# Power.net
KiCad netlist of a schematic drawn in Altium Designer
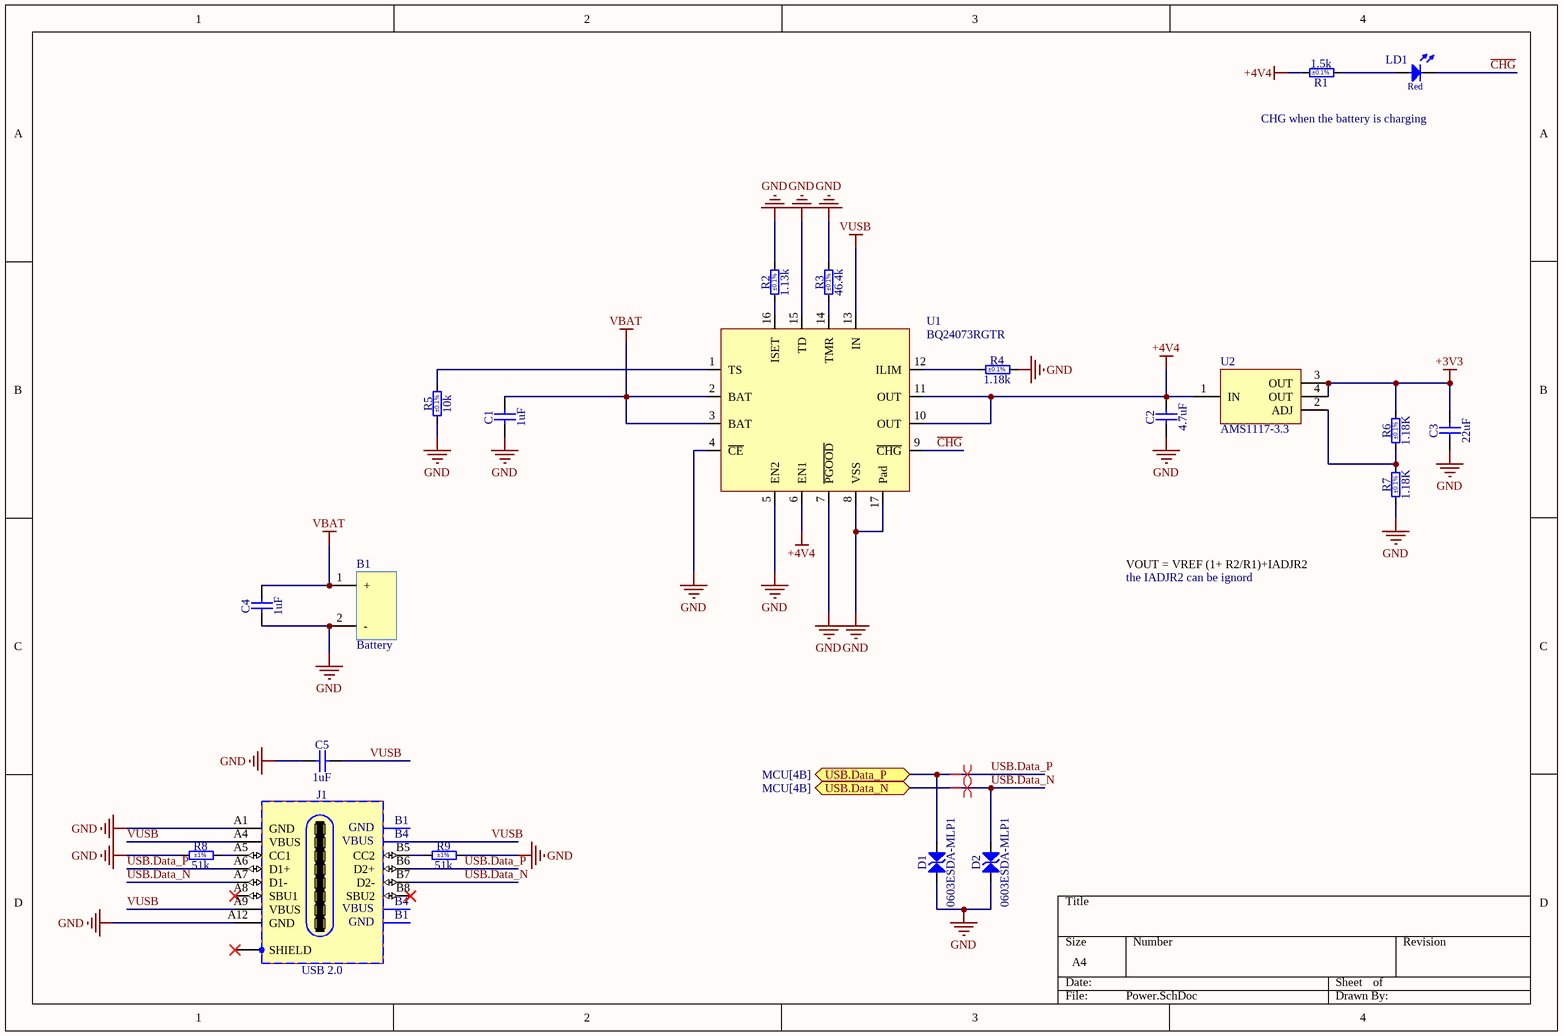
[diagram p0: Power.SchDoc]

(export (version "E")
  (design (tool "Eeschema 10.0.6"))
  (components
    (comp (ref "B1")
      (value "Battery")
      (footprint "PCB.Battery.Holder.14500")
      (description "PCB Battery Holder Embeded in PCB")
      (libsource (lib "ParsaAltiumSCHLIB") (part "PCB.Battery.Holder.14500"))
    )
    (comp (ref "C1")
      (value "1uF")
      (footprint "CAPC1608X90N")
      (description "Non-polarised capacitor")
      (fields
        (field (name "PART NUMBER") "CC0603_1UF_10V_10%_X5R")
        (field (name "VOLTAGE") "10V")
        (field (name "AUTHOR") "CERN DEM HF")
      )
      (libsource (lib "Capacitors") (part "Capacitor - non polarized"))
    )
    (comp (ref "C2")
      (value "4.7uF")
      (footprint "CAPC1608X90N")
      (description "Non-polarised capacitor")
      (fields
        (field (name "PART NUMBER") "CC0603_4.7UF_10V_10%_X5R")
        (field (name "VOLTAGE") "10V")
        (field (name "AUTHOR") "CERN DEM HF")
      )
      (libsource (lib "Capacitors") (part "Capacitor - non polarized"))
    )
    (comp (ref "C3")
      (value "22uF")
      (footprint "CAPC1608X90N")
      (description "Non-polarised capacitor")
      (fields
        (field (name "PART NUMBER") "CC0603_22UF_10V_20%_X5R")
        (field (name "VOLTAGE") "10V")
        (field (name "AUTHOR") "CERN DEM BC")
      )
      (libsource (lib "Capacitors") (part "Capacitor - non polarized"))
    )
    (comp (ref "C4")
      (value "1uF")
      (footprint "CAPC1608X90N")
      (description "Non-polarised capacitor")
      (fields
        (field (name "PART NUMBER") "CC0603_1UF_10V_10%_X5R")
        (field (name "VOLTAGE") "10V")
        (field (name "AUTHOR") "CERN DEM HF")
      )
      (libsource (lib "Capacitors") (part "Capacitor - non polarized"))
    )
    (comp (ref "C5")
      (value "1uF")
      (footprint "CAPC1608X90N")
      (description "Non-polarised capacitor")
      (fields
        (field (name "PART NUMBER") "CC0603_1UF_10V_10%_X5R")
        (field (name "VOLTAGE") "10V")
        (field (name "AUTHOR") "CERN DEM HF")
      )
      (libsource (lib "Capacitors") (part "Capacitor - non polarized"))
    )
    (comp (ref "D1")
      (value "0603ESDA-MLP1")
      (footprint "EATON_0603ESDA-MLP")
      (description "Transient Voltage Suppressor Diode (Bi-Directional)")
      (fields
        (field (name "VOLTAGE") "8kV")
        (field (name "MANUFACTURER") "EATON")
        (field (name "AUTHOR") "CERN DEM HF")
      )
      (libsource (lib "ICs And Semiconductors") (part "Diode TVS Bi-Directional"))
    )
    (comp (ref "D2")
      (value "0603ESDA-MLP1")
      (footprint "EATON_0603ESDA-MLP")
      (description "Transient Voltage Suppressor Diode (Bi-Directional)")
      (fields
        (field (name "VOLTAGE") "8kV")
        (field (name "MANUFACTURER") "EATON")
        (field (name "AUTHOR") "CERN DEM HF")
      )
      (libsource (lib "ICs And Semiconductors") (part "Diode TVS Bi-Directional"))
    )
    (comp (ref "J1")
      (value "USB 2.0")
      (footprint "GCT_USB4105-GF-A")
      (description "2x8 Pin + 1 Shield  USB Type C Receptacle")
      (fields
        (field (name "PART NUMBER") "GCT_USB4105-GF-A")
        (field (name "MANUFACTURER") "GCT")
        (field (name "AUTHOR") "CERN DEM HF")
      )
      (libsource (lib "Connectors") (part "GCT_USB4105-GF-A"))
    )
    (comp (ref "LD1")
      (value "Red")
      (footprint "LED_DIALIGHT_598-8010-107F")
      (description "LED Red 1C 2A")
      (fields
        (field (name "PART NUMBER") "LED_DIALIGHT_598-8010-107F")
        (field (name "MANUFACTURER") "DIALIGHT")
        (field (name "AUTHOR") "CERN DEM MR")
      )
      (libsource (lib "ICs And Semiconductors") (part "LED Red 1C 2A"))
    )
    (comp (ref "R1")
      (value "1.5k")
      (footprint "RESC1608X55N")
      (description "Resistor - 0.1%")
      (fields
        (field (name "TOLERANCE") "±0.1%")
        (field (name "PART NUMBER") "R0603_10K_0.1%_0.063W_10PPM")
        (field (name "POWER") "0.063W")
        (field (name "AUTHOR") "CERN DEM JLC")
      )
      (libsource (lib "Resistors") (part "Resistor - 0.1%"))
    )
    (comp (ref "R2")
      (value "1.13k")
      (footprint "RESC1608X55N")
      (description "Resistor - 0.1%")
      (fields
        (field (name "TOLERANCE") "±0.1%")
        (field (name "PART NUMBER") "R0603_10K_0.1%_0.063W_10PPM")
        (field (name "POWER") "0.063W")
        (field (name "AUTHOR") "CERN DEM JLC")
      )
      (libsource (lib "Resistors") (part "Resistor - 0.1%"))
    )
    (comp (ref "R3")
      (value "46.4k")
      (footprint "RESC1608X55N")
      (description "Resistor - 0.1%")
      (fields
        (field (name "TOLERANCE") "±0.1%")
        (field (name "PART NUMBER") "R0603_10K_0.1%_0.063W_10PPM")
        (field (name "POWER") "0.063W")
        (field (name "AUTHOR") "CERN DEM JLC")
      )
      (libsource (lib "Resistors") (part "Resistor - 0.1%"))
    )
    (comp (ref "R4")
      (value "1.18k")
      (footprint "RESC1608X55N")
      (description "Resistor - 0.1%")
      (fields
        (field (name "TOLERANCE") "±0.1%")
        (field (name "PART NUMBER") "R0603_10K_0.1%_0.063W_10PPM")
        (field (name "POWER") "0.063W")
        (field (name "AUTHOR") "CERN DEM JLC")
      )
      (libsource (lib "Resistors") (part "Resistor - 0.1%"))
    )
    (comp (ref "R5")
      (value "10k")
      (footprint "RESC1608X55N")
      (description "Resistor - 0.1%")
      (fields
        (field (name "TOLERANCE") "±0.1%")
        (field (name "PART NUMBER") "R0603_10K_0.1%_0.063W_10PPM")
        (field (name "POWER") "0.063W")
        (field (name "AUTHOR") "CERN DEM JLC")
      )
      (libsource (lib "Resistors") (part "Resistor - 0.1%"))
    )
    (comp (ref "R6")
      (value "1.18K")
      (footprint "RESC1608X55N")
      (description "Resistor - 0.1%")
      (fields
        (field (name "TOLERANCE") "±0.1%")
        (field (name "PART NUMBER") "R0603_118R_0.1%_0.063W_10PPM")
        (field (name "POWER") "0.063W")
        (field (name "AUTHOR") "CERN DEM JLC")
      )
      (libsource (lib "Resistors") (part "Resistor - 0.1%"))
    )
    (comp (ref "R7")
      (value "1.18K")
      (footprint "RESC1608X55N")
      (description "Resistor - 0.1%")
      (fields
        (field (name "TOLERANCE") "±0.1%")
        (field (name "PART NUMBER") "R0603_118R_0.1%_0.063W_10PPM")
        (field (name "POWER") "0.063W")
        (field (name "AUTHOR") "CERN DEM JLC")
      )
      (libsource (lib "Resistors") (part "Resistor - 0.1%"))
    )
    (comp (ref "R8")
      (value "51k")
      (footprint "RESC1608X55N")
      (description "Resistor - 1%")
      (fields
        (field (name "TOLERANCE") "±1%")
        (field (name "PART NUMBER") "R0603_51K_1%_0.1W_100PPM")
        (field (name "POWER") "0.1W")
        (field (name "AUTHOR") "CERN DEM JLC")
      )
      (libsource (lib "Resistors") (part "Resistor - 1%"))
    )
    (comp (ref "R9")
      (value "51k")
      (footprint "RESC1608X55N")
      (description "Resistor - 1%")
      (fields
        (field (name "TOLERANCE") "±1%")
        (field (name "PART NUMBER") "R0603_51K_1%_0.1W_100PPM")
        (field (name "POWER") "0.1W")
        (field (name "AUTHOR") "CERN DEM JLC")
      )
      (libsource (lib "Resistors") (part "Resistor - 1%"))
    )
    (comp (ref "U1")
      (value "BQ24073RGTR")
      (footprint "bq24073")
      (description "1.5A USB-FRIENDLY Li-Ion BATTERY CHARGER AND POWER-PATH MANAGEMENT IC")
      (libsource (lib "Schlib1") (part "BQ24073RGTR"))
    )
    (comp (ref "U2")
      (value "AMS1117-3.3")
      (footprint "IC.AMS1117-3.3")
      (description "72dB@(120Hz) 1A Fixed 3.3V Positive electrode SOT-223-3 Linear Voltage Regulators (LDO) ROHS")
      (libsource (lib "ParsaAltiumSCHLIB") (part "IC.AMS1117-3.3"))
    )
  )
  (nets
    (net (code "1") (name "+3V3") (class "Default")
      (node (ref "C3") (pin "2") (pinfunction "2_2") (pintype "passive"))
      (node (ref "R6") (pin "2") (pinfunction "2_2") (pintype "passive"))
      (node (ref "U2") (pin "3") (pinfunction "OUT_3") (pintype "passive"))
      (node (ref "U2") (pin "4") (pinfunction "OUT_4") (pintype "passive"))
    )
    (net (code "2") (name "+4V4") (class "Default")
      (node (ref "C2") (pin "2") (pinfunction "2_2") (pintype "passive"))
      (node (ref "R1") (pin "2") (pinfunction "2_2") (pintype "passive"))
      (node (ref "U1") (pin "10") (pinfunction "OUT_10") (pintype "passive"))
      (node (ref "U1") (pin "11") (pinfunction "OUT_11") (pintype "passive"))
      (node (ref "U1") (pin "6") (pinfunction "EN1_6") (pintype "passive"))
      (node (ref "U2") (pin "1") (pinfunction "IN_1") (pintype "passive"))
    )
    (net (code "3") (name "/USB.Data_N") (class "Default")
      (node (ref "D2") (pin "2") (pinfunction "2_2") (pintype "passive"))
      (node (ref "J1") (pin "A7") (pinfunction "D1-_A7") (pintype "bidirectional"))
      (node (ref "J1") (pin "B7") (pinfunction "D2-_B7") (pintype "bidirectional"))
    )
    (net (code "4") (name "/USB.Data_P") (class "Default")
      (node (ref "D1") (pin "2") (pinfunction "2_2") (pintype "passive"))
      (node (ref "J1") (pin "A6") (pinfunction "D1+_A6") (pintype "bidirectional"))
      (node (ref "J1") (pin "B6") (pinfunction "D2+_B6") (pintype "bidirectional"))
    )
    (net (code "5") (name "/~{CHG}") (class "Default")
      (node (ref "LD1") (pin "1") (pinfunction "C_1") (pintype "passive"))
      (node (ref "U1") (pin "9") (pinfunction "~{CHG}_9") (pintype "passive"))
    )
    (net (code "6") (name "GND") (class "Default")
      (node (ref "B1") (pin "2") (pinfunction "-_2") (pintype "passive"))
      (node (ref "C1") (pin "1") (pinfunction "1_1") (pintype "passive"))
      (node (ref "C2") (pin "1") (pinfunction "1_1") (pintype "passive"))
      (node (ref "C3") (pin "1") (pinfunction "1_1") (pintype "passive"))
      (node (ref "C4") (pin "1") (pinfunction "1_1") (pintype "passive"))
      (node (ref "C5") (pin "1") (pinfunction "1_1") (pintype "passive"))
      (node (ref "D1") (pin "1") (pinfunction "1_1") (pintype "passive"))
      (node (ref "D2") (pin "1") (pinfunction "1_1") (pintype "passive"))
      (node (ref "J1") (pin "A1") (pinfunction "GND_A1") (pintype "power_in"))
      (node (ref "J1") (pin "A12") (pinfunction "GND_A12") (pintype "power_in"))
      (node (ref "R2") (pin "2") (pinfunction "2_2") (pintype "passive"))
      (node (ref "R3") (pin "2") (pinfunction "2_2") (pintype "passive"))
      (node (ref "R4") (pin "2") (pinfunction "2_2") (pintype "passive"))
      (node (ref "R5") (pin "1") (pinfunction "1_1") (pintype "passive"))
      (node (ref "R7") (pin "1") (pinfunction "1_1") (pintype "passive"))
      (node (ref "R8") (pin "1") (pinfunction "1_1") (pintype "passive"))
      (node (ref "R9") (pin "2") (pinfunction "2_2") (pintype "passive"))
      (node (ref "U1") (pin "15") (pinfunction "TD_15") (pintype "passive"))
      (node (ref "U1") (pin "17") (pinfunction "Pad_17") (pintype "passive"))
      (node (ref "U1") (pin "4") (pinfunction "~{CE}_4") (pintype "passive"))
      (node (ref "U1") (pin "5") (pinfunction "EN2_5") (pintype "passive"))
      (node (ref "U1") (pin "7") (pinfunction "~{PGOOD}_7") (pintype "passive"))
      (node (ref "U1") (pin "8") (pinfunction "VSS_8") (pintype "passive"))
    )
    (net (code "7") (name "Net-(J1-CC1)") (class "Default")
      (node (ref "J1") (pin "A5") (pinfunction "CC1_A5") (pintype "bidirectional"))
      (node (ref "R8") (pin "2") (pinfunction "2_2") (pintype "passive"))
    )
    (net (code "8") (name "Net-(J1-CC2)") (class "Default")
      (node (ref "J1") (pin "B5") (pinfunction "CC2_B5") (pintype "bidirectional"))
      (node (ref "R9") (pin "1") (pinfunction "1_1") (pintype "passive"))
    )
    (net (code "9") (name "Net-(LD1-A)") (class "Default")
      (node (ref "LD1") (pin "2") (pinfunction "A_2") (pintype "passive"))
      (node (ref "R1") (pin "1") (pinfunction "1_1") (pintype "passive"))
    )
    (net (code "10") (name "Net-(U1-ILIM)") (class "Default")
      (node (ref "R4") (pin "1") (pinfunction "1_1") (pintype "passive"))
      (node (ref "U1") (pin "12") (pinfunction "ILIM_12") (pintype "passive"))
    )
    (net (code "11") (name "Net-(U1-ISET)") (class "Default")
      (node (ref "R2") (pin "1") (pinfunction "1_1") (pintype "passive"))
      (node (ref "U1") (pin "16") (pinfunction "ISET_16") (pintype "passive"))
    )
    (net (code "12") (name "Net-(U1-TMR)") (class "Default")
      (node (ref "R3") (pin "1") (pinfunction "1_1") (pintype "passive"))
      (node (ref "U1") (pin "14") (pinfunction "TMR_14") (pintype "passive"))
    )
    (net (code "13") (name "Net-(U1-TS)") (class "Default")
      (node (ref "R5") (pin "2") (pinfunction "2_2") (pintype "passive"))
      (node (ref "U1") (pin "1") (pinfunction "TS_1") (pintype "passive"))
    )
    (net (code "14") (name "Net-(U2-ADJ)") (class "Default")
      (node (ref "R6") (pin "1") (pinfunction "1_1") (pintype "passive"))
      (node (ref "R7") (pin "2") (pinfunction "2_2") (pintype "passive"))
      (node (ref "U2") (pin "2") (pinfunction "ADJ_2") (pintype "passive"))
    )
    (net (code "15") (name "VBAT") (class "Default")
      (node (ref "B1") (pin "1") (pinfunction "+_1") (pintype "passive"))
      (node (ref "C1") (pin "2") (pinfunction "2_2") (pintype "passive"))
      (node (ref "C4") (pin "2") (pinfunction "2_2") (pintype "passive"))
      (node (ref "U1") (pin "2") (pinfunction "BAT_2") (pintype "passive"))
      (node (ref "U1") (pin "3") (pinfunction "BAT_3") (pintype "passive"))
    )
    (net (code "16") (name "VUSB") (class "Default")
      (node (ref "C5") (pin "2") (pinfunction "2_2") (pintype "passive"))
      (node (ref "J1") (pin "A4") (pinfunction "VBUS_A4") (pintype "power_in"))
      (node (ref "J1") (pin "A9") (pinfunction "VBUS_A9") (pintype "power_in"))
      (node (ref "U1") (pin "13") (pinfunction "IN_13") (pintype "passive"))
    )
    (net (code "17") (name "unconnected-(J1-PadSHIELD)") (class "Default")
      (node (ref "J1") (pin "SHIELD") (pinfunction "SHIELD_SHIELD") (pintype "power_in+no_connect"))
    )
    (net (code "18") (name "unconnected-(J1-SBU1-PadA8)") (class "Default")
      (node (ref "J1") (pin "A8") (pinfunction "SBU1_A8") (pintype "bidirectional+no_connect"))
    )
    (net (code "19") (name "unconnected-(J1-SBU2-PadB8)") (class "Default")
      (node (ref "J1") (pin "B8") (pinfunction "SBU2_B8") (pintype "bidirectional+no_connect"))
    )
  )
)
